# BOOSTXL-EDUMKII.net
KiCad netlist of a schematic drawn in EAGLE
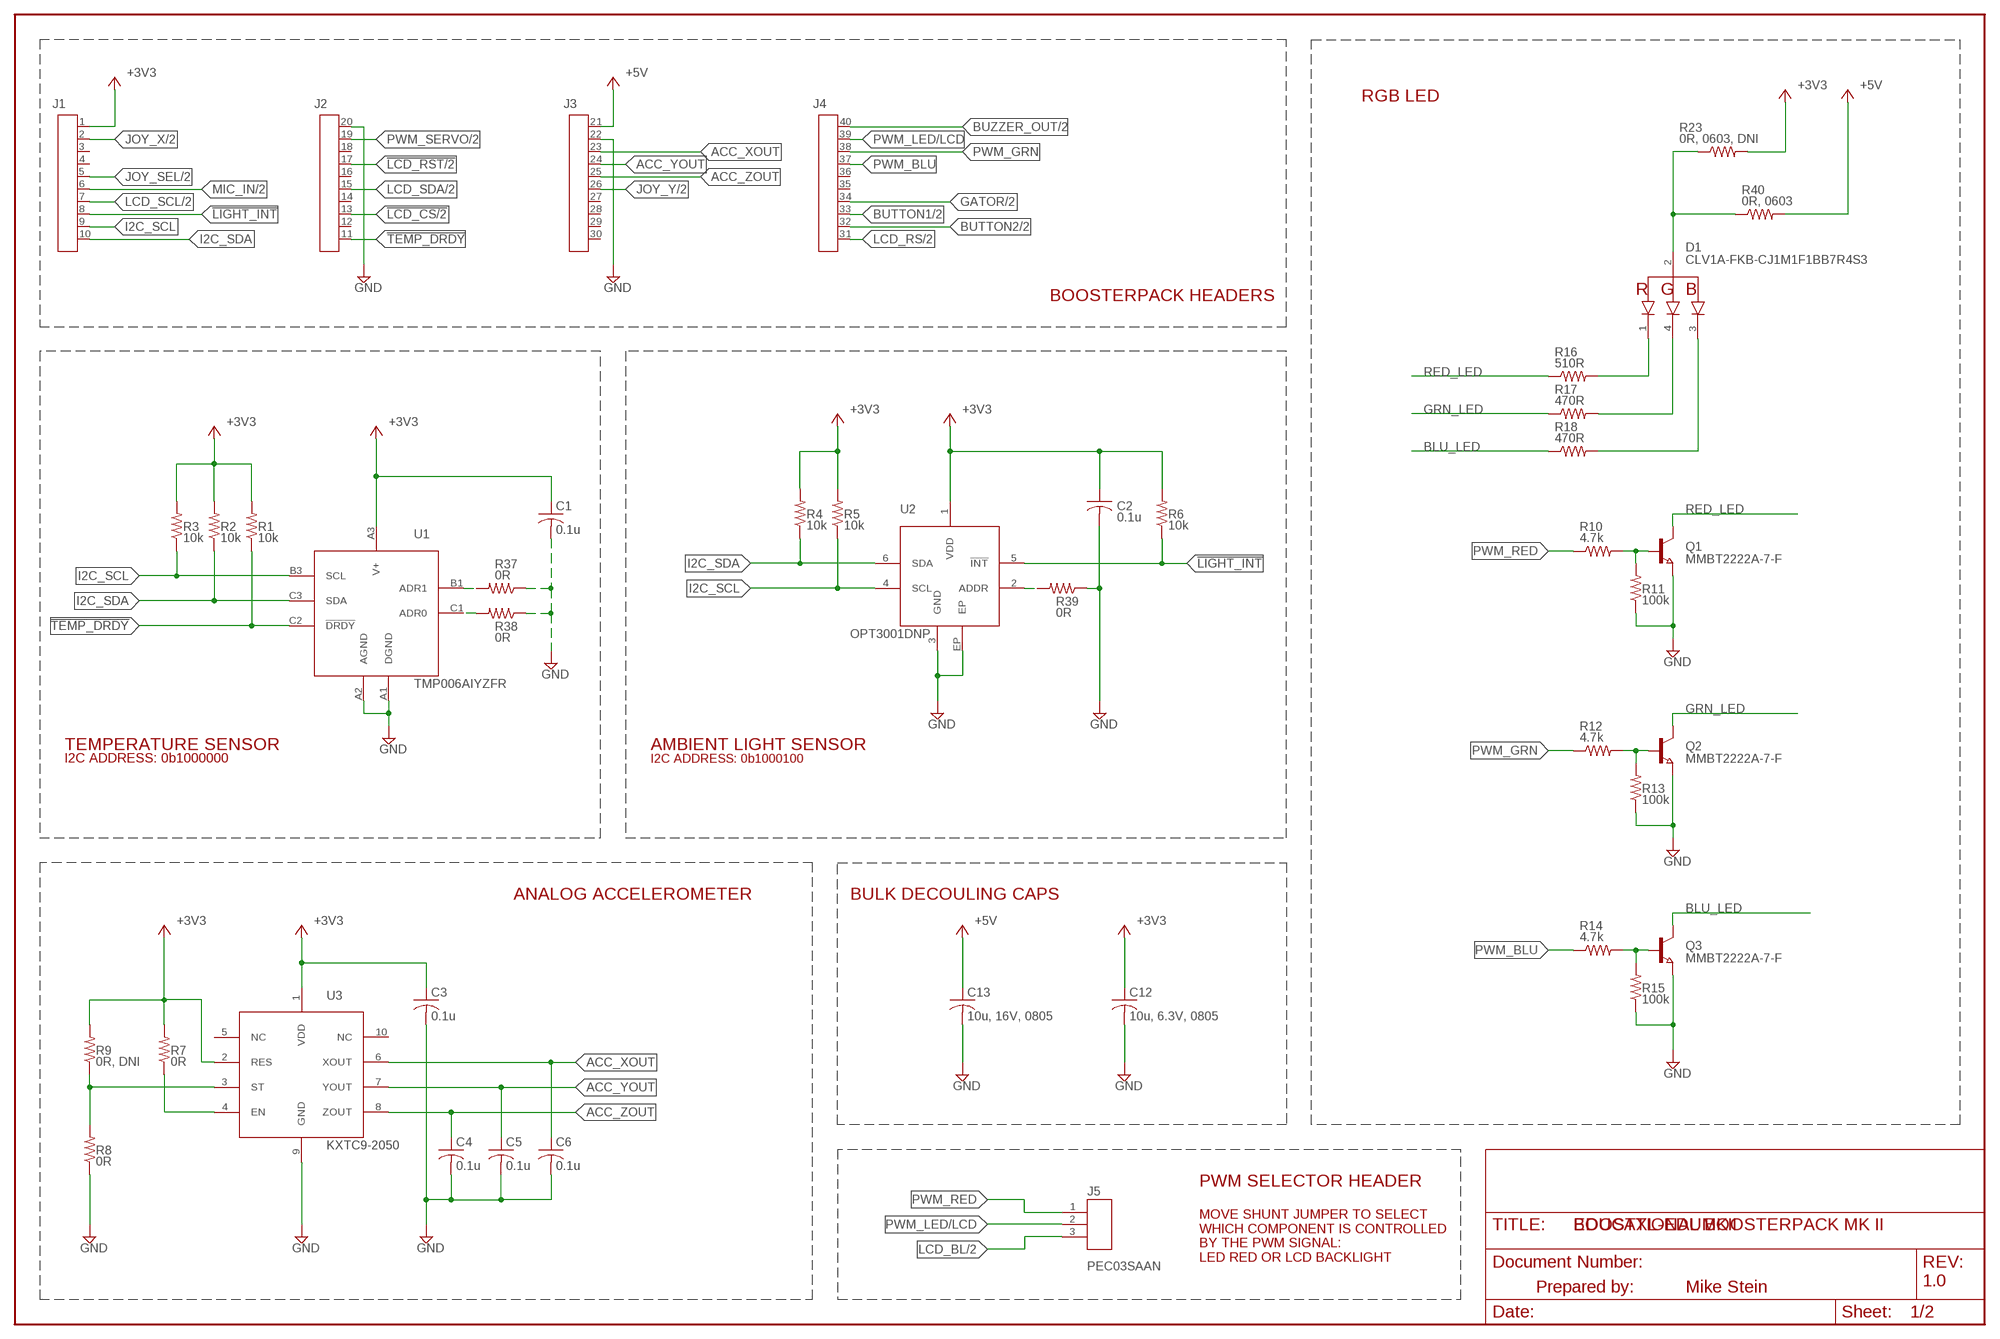
[diagram p0: schematic, sheet 1]
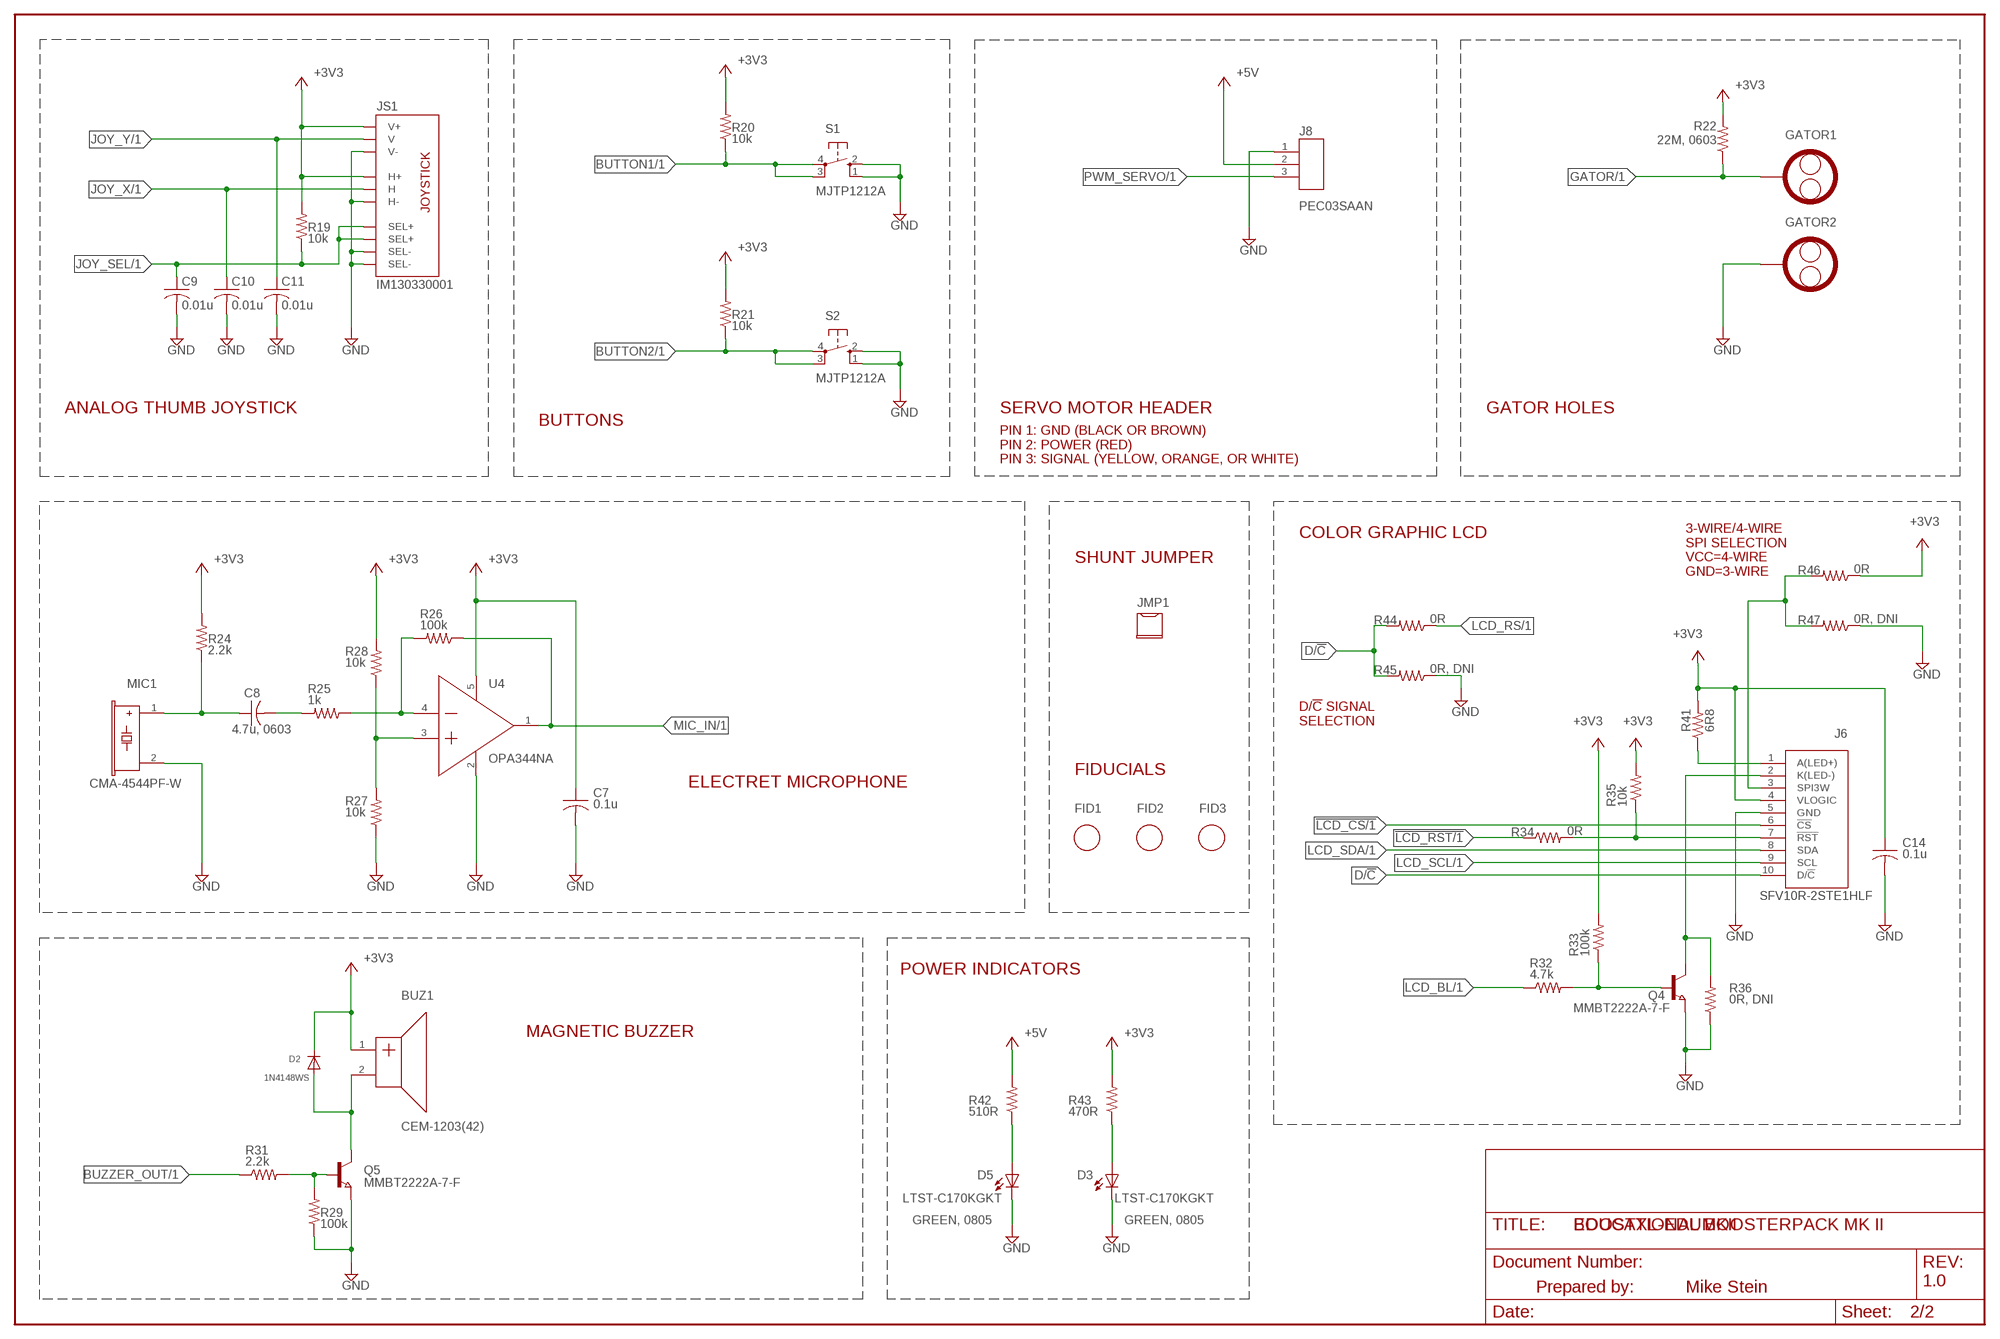
[diagram p1: schematic, sheet 2]

(export (version "E")
  (design (tool "Eeschema 10.0.6"))
  (components
    (comp (ref "C1")
      (value "0.1u")
      (footprint "eagle-import:0402")
      (libsource (lib "eagle-import") (part "C-USCM0402"))
    )
    (comp (ref "C2")
      (value "0.1u")
      (footprint "eagle-import:0402")
      (libsource (lib "eagle-import") (part "C-USCM0402"))
    )
    (comp (ref "C3")
      (value "0.1u")
      (footprint "eagle-import:0402")
      (libsource (lib "eagle-import") (part "C-USCM0402"))
    )
    (comp (ref "C4")
      (value "0.1u")
      (footprint "eagle-import:0402")
      (libsource (lib "eagle-import") (part "C-USCM0402"))
    )
    (comp (ref "C5")
      (value "0.1u")
      (footprint "eagle-import:0402")
      (libsource (lib "eagle-import") (part "C-USCM0402"))
    )
    (comp (ref "C6")
      (value "0.1u")
      (footprint "eagle-import:0402")
      (libsource (lib "eagle-import") (part "C-USCM0402"))
    )
    (comp (ref "C12")
      (value "10u, 6.3V, 0805")
      (footprint "eagle-import:C0805")
      (libsource (lib "eagle-import") (part "rcl_C-USC0805"))
    )
    (comp (ref "C13")
      (value "10u, 16V, 0805")
      (footprint "eagle-import:C0805")
      (libsource (lib "eagle-import") (part "rcl_C-USC0805"))
    )
    (comp (ref "D1")
      (value "CLV1A-FKB-CJ1M1F1BB7R4S3")
      (footprint "eagle-import:CLV1A-FKB")
      (libsource (lib "eagle-import") (part "CLV1A-FKB"))
    )
    (comp (ref "J1")
      (value "HEADER1X10")
      (footprint "eagle-import:1X10")
      (libsource (lib "eagle-import") (part "HEADER1X10"))
    )
    (comp (ref "J2")
      (value "HEADER1X10-J2")
      (footprint "eagle-import:1X10-J2")
      (libsource (lib "eagle-import") (part "HEADER1X10-J2"))
    )
    (comp (ref "J3")
      (value "HEADER1X10-J3")
      (footprint "eagle-import:1X10-J3")
      (libsource (lib "eagle-import") (part "HEADER1X10-J3"))
    )
    (comp (ref "J4")
      (value "HEADER1X10-J4")
      (footprint "eagle-import:1X10-J4")
      (libsource (lib "eagle-import") (part "HEADER1X10-J4"))
    )
    (comp (ref "J5")
      (value "PEC03SAAN")
      (footprint "eagle-import:1X03")
      (libsource (lib "eagle-import") (part "HEADER1X03"))
    )
    (comp (ref "Q1")
      (value "MMBT2222A-7-F")
      (footprint "eagle-import:SOT23")
      (libsource (lib "eagle-import") (part "NPN-TRANSISTOR_SOT23"))
    )
    (comp (ref "Q2")
      (value "MMBT2222A-7-F")
      (footprint "eagle-import:SOT23")
      (libsource (lib "eagle-import") (part "NPN-TRANSISTOR_SOT23"))
    )
    (comp (ref "Q3")
      (value "MMBT2222A-7-F")
      (footprint "eagle-import:SOT23")
      (libsource (lib "eagle-import") (part "NPN-TRANSISTOR_SOT23"))
    )
    (comp (ref "R1")
      (value "10k")
      (footprint "eagle-import:0402")
      (libsource (lib "eagle-import") (part "R-US_RM0402"))
    )
    (comp (ref "R2")
      (value "10k")
      (footprint "eagle-import:0402")
      (libsource (lib "eagle-import") (part "R-US_RM0402"))
    )
    (comp (ref "R3")
      (value "10k")
      (footprint "eagle-import:0402")
      (libsource (lib "eagle-import") (part "R-US_RM0402"))
    )
    (comp (ref "R4")
      (value "10k")
      (footprint "eagle-import:0402")
      (libsource (lib "eagle-import") (part "R-US_RM0402"))
    )
    (comp (ref "R5")
      (value "10k")
      (footprint "eagle-import:0402")
      (libsource (lib "eagle-import") (part "R-US_RM0402"))
    )
    (comp (ref "R6")
      (value "10k")
      (footprint "eagle-import:0402")
      (libsource (lib "eagle-import") (part "R-US_RM0402"))
    )
    (comp (ref "R7")
      (value "0R")
      (footprint "eagle-import:0402")
      (libsource (lib "eagle-import") (part "R-US_RM0402"))
    )
    (comp (ref "R8")
      (value "0R")
      (footprint "eagle-import:0402")
      (libsource (lib "eagle-import") (part "R-US_RM0402"))
    )
    (comp (ref "R9")
      (value "0R, DNI")
      (footprint "eagle-import:0402")
      (libsource (lib "eagle-import") (part "R-US_RM0402"))
    )
    (comp (ref "R10")
      (value "4.7k")
      (footprint "eagle-import:0402")
      (libsource (lib "eagle-import") (part "R-US_RM0402"))
    )
    (comp (ref "R11")
      (value "100k")
      (footprint "eagle-import:0402")
      (libsource (lib "eagle-import") (part "R-US_RM0402"))
    )
    (comp (ref "R12")
      (value "4.7k")
      (footprint "eagle-import:0402")
      (libsource (lib "eagle-import") (part "R-US_RM0402"))
    )
    (comp (ref "R13")
      (value "100k")
      (footprint "eagle-import:0402")
      (libsource (lib "eagle-import") (part "R-US_RM0402"))
    )
    (comp (ref "R14")
      (value "4.7k")
      (footprint "eagle-import:0402")
      (libsource (lib "eagle-import") (part "R-US_RM0402"))
    )
    (comp (ref "R15")
      (value "100k")
      (footprint "eagle-import:0402")
      (libsource (lib "eagle-import") (part "R-US_RM0402"))
    )
    (comp (ref "R16")
      (value "510R")
      (footprint "eagle-import:0402")
      (libsource (lib "eagle-import") (part "R-US_RM0402"))
    )
    (comp (ref "R17")
      (value "470R")
      (footprint "eagle-import:0402")
      (libsource (lib "eagle-import") (part "R-US_RM0402"))
    )
    (comp (ref "R18")
      (value "470R")
      (footprint "eagle-import:0402")
      (libsource (lib "eagle-import") (part "R-US_RM0402"))
    )
    (comp (ref "R23")
      (value "0R, 0603, DNI")
      (footprint "eagle-import:R0603")
      (libsource (lib "eagle-import") (part "R-US_R0603"))
    )
    (comp (ref "R37")
      (value "0R")
      (footprint "eagle-import:0402")
      (libsource (lib "eagle-import") (part "R-US_RM0402"))
    )
    (comp (ref "R38")
      (value "0R")
      (footprint "eagle-import:0402")
      (libsource (lib "eagle-import") (part "R-US_RM0402"))
    )
    (comp (ref "R39")
      (value "0R")
      (footprint "eagle-import:0402")
      (libsource (lib "eagle-import") (part "R-US_RM0402"))
    )
    (comp (ref "R40")
      (value "0R, 0603")
      (footprint "eagle-import:R0603")
      (libsource (lib "eagle-import") (part "R-US_R0603"))
    )
    (comp (ref "U1")
      (value "TMP006AIYZFR")
      (footprint "eagle-import:YZF_S-XBGA-N8")
      (libsource (lib "eagle-import") (part "TMP006AIYZF"))
    )
    (comp (ref "U2")
      (value "OPT3001DNP")
      (footprint "eagle-import:DNP_S-PWSON-N6")
      (libsource (lib "eagle-import") (part "OPT3001DNP"))
    )
    (comp (ref "U3")
      (value "KXTC9-2050")
      (footprint "eagle-import:KXTC9-2050")
      (libsource (lib "eagle-import") (part "KXTC9-2050"))
    )
    (comp (ref "BUZ1")
      (value "CEM-1203(42)")
      (footprint "eagle-import:CEM-1203(42)")
      (libsource (lib "eagle-import") (part "CEM-1203(42)"))
    )
    (comp (ref "C7")
      (value "0.1u")
      (footprint "eagle-import:0402")
      (libsource (lib "eagle-import") (part "C-USCM0402"))
    )
    (comp (ref "C8")
      (value "4.7u, 0603")
      (footprint "eagle-import:C0603")
      (libsource (lib "eagle-import") (part "C-USC0603"))
    )
    (comp (ref "C9")
      (value "0.01u")
      (footprint "eagle-import:0402")
      (libsource (lib "eagle-import") (part "C-USCM0402"))
    )
    (comp (ref "C10")
      (value "0.01u")
      (footprint "eagle-import:0402")
      (libsource (lib "eagle-import") (part "C-USCM0402"))
    )
    (comp (ref "C11")
      (value "0.01u")
      (footprint "eagle-import:0402")
      (libsource (lib "eagle-import") (part "C-USCM0402"))
    )
    (comp (ref "C14")
      (value "0.1u")
      (footprint "eagle-import:0402")
      (libsource (lib "eagle-import") (part "C-USCM0402"))
    )
    (comp (ref "D2")
      (value "1N4148WS")
      (footprint "eagle-import:SOD-323F")
      (libsource (lib "eagle-import") (part "DIODE"))
    )
    (comp (ref "D3")
      (value "LTST-C170KGKT")
      (footprint "eagle-import:LED-CHIP0805")
      (libsource (lib "eagle-import") (part "LED"))
    )
    (comp (ref "D5")
      (value "LTST-C170KGKT")
      (footprint "eagle-import:LED-CHIP0805")
      (libsource (lib "eagle-import") (part "LED"))
    )
    (comp (ref "FID1")
      (value "FIDUCIAL")
      (footprint "eagle-import:FIDUCIAL_1MM")
      (libsource (lib "eagle-import") (part "FIDUCIAL"))
    )
    (comp (ref "FID2")
      (value "FIDUCIAL")
      (footprint "eagle-import:FIDUCIAL_1MM")
      (libsource (lib "eagle-import") (part "FIDUCIAL"))
    )
    (comp (ref "FID3")
      (value "FIDUCIAL")
      (footprint "eagle-import:FIDUCIAL_1MM")
      (libsource (lib "eagle-import") (part "FIDUCIAL"))
    )
    (comp (ref "GATOR1")
      (value "GATOR_HOLE")
      (footprint "eagle-import:GATOR-HOLE-3MM")
      (libsource (lib "eagle-import") (part "GATOR_HOLE"))
    )
    (comp (ref "GATOR2")
      (value "GATOR_HOLE")
      (footprint "eagle-import:GATOR-HOLE-3MM")
      (libsource (lib "eagle-import") (part "GATOR_HOLE"))
    )
    (comp (ref "J6")
      (value "SFV10R-2STE1HLF")
      (footprint "eagle-import:SFV10R-2STE1HLF")
      (libsource (lib "eagle-import") (part "SFV10R-2STE1HLF"))
    )
    (comp (ref "J8")
      (value "PEC03SAAN")
      (footprint "eagle-import:1X03")
      (libsource (lib "eagle-import") (part "HEADER1X03"))
    )
    (comp (ref "JS1")
      (value "IM130330001")
      (footprint "eagle-import:JOYSTICK-SW")
      (libsource (lib "eagle-import") (part "JOYSTICK-SW"))
    )
    (comp (ref "MIC1")
      (value "CMA-4544PF-W")
      (footprint "eagle-import:CMA-4544PF-W")
      (libsource (lib "eagle-import") (part "CMA-4544PF-W"))
    )
    (comp (ref "Q4")
      (value "MMBT2222A-7-F")
      (footprint "eagle-import:SOT23")
      (libsource (lib "eagle-import") (part "NPN-TRANSISTOR_SOT23"))
    )
    (comp (ref "Q5")
      (value "MMBT2222A-7-F")
      (footprint "eagle-import:SOT23")
      (libsource (lib "eagle-import") (part "NPN-TRANSISTOR_SOT23"))
    )
    (comp (ref "R19")
      (value "10k")
      (footprint "eagle-import:0402")
      (libsource (lib "eagle-import") (part "R-US_RM0402"))
    )
    (comp (ref "R20")
      (value "10k")
      (footprint "eagle-import:0402")
      (libsource (lib "eagle-import") (part "R-US_RM0402"))
    )
    (comp (ref "R21")
      (value "10k")
      (footprint "eagle-import:0402")
      (libsource (lib "eagle-import") (part "R-US_RM0402"))
    )
    (comp (ref "R22")
      (value "22M, 0603")
      (footprint "eagle-import:R0603")
      (libsource (lib "eagle-import") (part "R-US_R0603"))
    )
    (comp (ref "R24")
      (value "2.2k")
      (footprint "eagle-import:0402")
      (libsource (lib "eagle-import") (part "R-US_RM0402"))
    )
    (comp (ref "R25")
      (value "1k")
      (footprint "eagle-import:0402")
      (libsource (lib "eagle-import") (part "R-US_RM0402"))
    )
    (comp (ref "R26")
      (value "100k")
      (footprint "eagle-import:0402")
      (libsource (lib "eagle-import") (part "R-US_RM0402"))
    )
    (comp (ref "R27")
      (value "10k")
      (footprint "eagle-import:0402")
      (libsource (lib "eagle-import") (part "R-US_RM0402"))
    )
    (comp (ref "R28")
      (value "10k")
      (footprint "eagle-import:0402")
      (libsource (lib "eagle-import") (part "R-US_RM0402"))
    )
    (comp (ref "R29")
      (value "100k")
      (footprint "eagle-import:0402")
      (libsource (lib "eagle-import") (part "R-US_RM0402"))
    )
    (comp (ref "R31")
      (value "2.2k")
      (footprint "eagle-import:0402")
      (libsource (lib "eagle-import") (part "R-US_RM0402"))
    )
    (comp (ref "R32")
      (value "4.7k")
      (footprint "eagle-import:0402")
      (libsource (lib "eagle-import") (part "R-US_RM0402"))
    )
    (comp (ref "R33")
      (value "100k")
      (footprint "eagle-import:0402")
      (libsource (lib "eagle-import") (part "R-US_RM0402"))
    )
    (comp (ref "R34")
      (value "0R")
      (footprint "eagle-import:0402")
      (libsource (lib "eagle-import") (part "R-US_RM0402"))
    )
    (comp (ref "R35")
      (value "10k")
      (footprint "eagle-import:0402")
      (libsource (lib "eagle-import") (part "R-US_RM0402"))
    )
    (comp (ref "R36")
      (value "0R, DNI")
      (footprint "eagle-import:0402")
      (libsource (lib "eagle-import") (part "R-US_RM0402"))
    )
    (comp (ref "R41")
      (value "6R8")
      (footprint "eagle-import:0402")
      (libsource (lib "eagle-import") (part "R-US_RM0402"))
    )
    (comp (ref "R42")
      (value "510R")
      (footprint "eagle-import:0402")
      (libsource (lib "eagle-import") (part "R-US_RM0402"))
    )
    (comp (ref "R43")
      (value "470R")
      (footprint "eagle-import:0402")
      (libsource (lib "eagle-import") (part "R-US_RM0402"))
    )
    (comp (ref "R44")
      (value "0R")
      (footprint "eagle-import:0402")
      (libsource (lib "eagle-import") (part "R-US_RM0402"))
    )
    (comp (ref "R45")
      (value "0R, DNI")
      (footprint "eagle-import:0402")
      (libsource (lib "eagle-import") (part "R-US_RM0402"))
    )
    (comp (ref "R46")
      (value "0R")
      (footprint "eagle-import:0402")
      (libsource (lib "eagle-import") (part "R-US_RM0402"))
    )
    (comp (ref "R47")
      (value "0R, DNI")
      (footprint "eagle-import:0402")
      (libsource (lib "eagle-import") (part "R-US_RM0402"))
    )
    (comp (ref "S1")
      (value "MJTP1212A")
      (footprint "eagle-import:TACTILE-MJTP")
      (libsource (lib "eagle-import") (part "SWITCH-MJTP"))
    )
    (comp (ref "S2")
      (value "MJTP1212A")
      (footprint "eagle-import:TACTILE-MJTP")
      (libsource (lib "eagle-import") (part "SWITCH-MJTP"))
    )
    (comp (ref "U4")
      (value "OPA344NA")
      (footprint "eagle-import:DBV_R-PDSO-G5")
      (libsource (lib "eagle-import") (part "OPA344NA"))
    )
  )
  (nets
    (net (code "1") (name "+3V3") (class "Default")
      (node (ref "BUZ1") (pin "1") (pinfunction "SPKR_P_1") (pintype "passive"))
      (node (ref "C1") (pin "1") (pinfunction "1_1") (pintype "passive"))
      (node (ref "C12") (pin "1") (pinfunction "1_1") (pintype "passive"))
      (node (ref "C14") (pin "1") (pinfunction "1_1") (pintype "passive"))
      (node (ref "C2") (pin "1") (pinfunction "1_1") (pintype "passive"))
      (node (ref "C3") (pin "1") (pinfunction "1_1") (pintype "passive"))
      (node (ref "C7") (pin "1") (pinfunction "1_1") (pintype "passive"))
      (node (ref "D2") (pin "C") (pinfunction "C_C") (pintype "passive"))
      (node (ref "J1") (pin "1") (pinfunction "1_1") (pintype "bidirectional"))
      (node (ref "J6") (pin "4") (pinfunction "VLOGIC_4") (pintype "power_in"))
      (node (ref "JS1") (pin "H+") (pinfunction "H+_H+") (pintype "bidirectional"))
      (node (ref "JS1") (pin "V+") (pinfunction "V+_V+") (pintype "bidirectional"))
      (node (ref "R1") (pin "2") (pinfunction "2_2") (pintype "passive"))
      (node (ref "R19") (pin "2") (pinfunction "2_2") (pintype "passive"))
      (node (ref "R2") (pin "2") (pinfunction "2_2") (pintype "passive"))
      (node (ref "R20") (pin "2") (pinfunction "2_2") (pintype "passive"))
      (node (ref "R21") (pin "2") (pinfunction "2_2") (pintype "passive"))
      (node (ref "R22") (pin "2") (pinfunction "2_2") (pintype "passive"))
      (node (ref "R23") (pin "2") (pinfunction "2_2") (pintype "passive"))
      (node (ref "R24") (pin "2") (pinfunction "2_2") (pintype "passive"))
      (node (ref "R28") (pin "2") (pinfunction "2_2") (pintype "passive"))
      (node (ref "R3") (pin "2") (pinfunction "2_2") (pintype "passive"))
      (node (ref "R33") (pin "2") (pinfunction "2_2") (pintype "passive"))
      (node (ref "R35") (pin "2") (pinfunction "2_2") (pintype "passive"))
      (node (ref "R4") (pin "2") (pinfunction "2_2") (pintype "passive"))
      (node (ref "R41") (pin "2") (pinfunction "2_2") (pintype "passive"))
      (node (ref "R43") (pin "2") (pinfunction "2_2") (pintype "passive"))
      (node (ref "R46") (pin "1") (pinfunction "1_1") (pintype "passive"))
      (node (ref "R5") (pin "2") (pinfunction "2_2") (pintype "passive"))
      (node (ref "R6") (pin "2") (pinfunction "2_2") (pintype "passive"))
      (node (ref "R7") (pin "2") (pinfunction "2_2") (pintype "passive"))
      (node (ref "R9") (pin "2") (pinfunction "2_2") (pintype "passive"))
      (node (ref "U1") (pin "A3") (pinfunction "V+_A3") (pintype "power_in"))
      (node (ref "U2") (pin "1") (pinfunction "VDD_1") (pintype "power_in"))
      (node (ref "U3") (pin "1") (pinfunction "VDD_1") (pintype "power_in"))
      (node (ref "U3") (pin "2") (pinfunction "RES_2") (pintype "power_in"))
      (node (ref "U4") (pin "5") (pinfunction "V+_5") (pintype "power_in"))
    )
    (net (code "2") (name "+5V") (class "Default")
      (node (ref "C13") (pin "1") (pinfunction "1_1") (pintype "passive"))
      (node (ref "J3") (pin "21") (pinfunction "1_21") (pintype "bidirectional"))
      (node (ref "J8") (pin "2") (pinfunction "2_2") (pintype "bidirectional"))
      (node (ref "R40") (pin "2") (pinfunction "2_2") (pintype "passive"))
      (node (ref "R42") (pin "2") (pinfunction "2_2") (pintype "passive"))
    )
    (net (code "3") (name "ACC_XOUT") (class "Default")
      (node (ref "C6") (pin "1") (pinfunction "1_1") (pintype "passive"))
      (node (ref "J3") (pin "23") (pinfunction "3_23") (pintype "bidirectional"))
      (node (ref "U3") (pin "6") (pinfunction "XOUT_6") (pintype "output"))
    )
    (net (code "4") (name "ACC_YOUT") (class "Default")
      (node (ref "C5") (pin "1") (pinfunction "1_1") (pintype "passive"))
      (node (ref "J3") (pin "24") (pinfunction "4_24") (pintype "bidirectional"))
      (node (ref "U3") (pin "7") (pinfunction "YOUT_7") (pintype "output"))
    )
    (net (code "5") (name "ACC_ZOUT") (class "Default")
      (node (ref "C4") (pin "1") (pinfunction "1_1") (pintype "passive"))
      (node (ref "J3") (pin "25") (pinfunction "5_25") (pintype "bidirectional"))
      (node (ref "U3") (pin "8") (pinfunction "ZOUT_8") (pintype "output"))
    )
    (net (code "6") (name "BLU_LED") (class "Default")
      (node (ref "Q3") (pin "3") (pinfunction "C_3") (pintype "passive"))
      (node (ref "R18") (pin "1") (pinfunction "1_1") (pintype "passive"))
    )
    (net (code "7") (name "BUTTON1") (class "Default")
      (node (ref "J4") (pin "33") (pinfunction "8_33") (pintype "bidirectional"))
      (node (ref "R20") (pin "1") (pinfunction "1_1") (pintype "passive"))
      (node (ref "S1") (pin "3") (pinfunction "P1_3") (pintype "passive"))
      (node (ref "S1") (pin "4") (pinfunction "P_4") (pintype "passive"))
    )
    (net (code "8") (name "BUTTON2") (class "Default")
      (node (ref "J4") (pin "32") (pinfunction "9_32") (pintype "bidirectional"))
      (node (ref "R21") (pin "1") (pinfunction "1_1") (pintype "passive"))
      (node (ref "S2") (pin "3") (pinfunction "P1_3") (pintype "passive"))
      (node (ref "S2") (pin "4") (pinfunction "P_4") (pintype "passive"))
    )
    (net (code "9") (name "BUZZER_OUT") (class "Default")
      (node (ref "J4") (pin "40") (pinfunction "1_40") (pintype "bidirectional"))
      (node (ref "R31") (pin "1") (pinfunction "1_1") (pintype "passive"))
    )
    (net (code "10") (name "D{slash}~{C}") (class "Default")
      (node (ref "J6") (pin "10") (pinfunction "D/~{C}_10") (pintype "bidirectional"))
      (node (ref "R44") (pin "2") (pinfunction "2_2") (pintype "passive"))
      (node (ref "R45") (pin "2") (pinfunction "2_2") (pintype "passive"))
    )
    (net (code "11") (name "GATOR") (class "Default")
      (node (ref "GATOR1") (pin "1@1") (pinfunction "P$1_1@1") (pintype "bidirectional"))
      (node (ref "J4") (pin "34") (pinfunction "7_34") (pintype "bidirectional"))
      (node (ref "R22") (pin "1") (pinfunction "1_1") (pintype "passive"))
    )
    (net (code "12") (name "GND") (class "Default")
      (node (ref "C1") (pin "2") (pinfunction "2_2") (pintype "passive"))
      (node (ref "C10") (pin "2") (pinfunction "2_2") (pintype "passive"))
      (node (ref "C11") (pin "2") (pinfunction "2_2") (pintype "passive"))
      (node (ref "C12") (pin "2") (pinfunction "2_2") (pintype "passive"))
      (node (ref "C13") (pin "2") (pinfunction "2_2") (pintype "passive"))
      (node (ref "C14") (pin "2") (pinfunction "2_2") (pintype "passive"))
      (node (ref "C2") (pin "2") (pinfunction "2_2") (pintype "passive"))
      (node (ref "C3") (pin "2") (pinfunction "2_2") (pintype "passive"))
      (node (ref "C4") (pin "2") (pinfunction "2_2") (pintype "passive"))
      (node (ref "C5") (pin "2") (pinfunction "2_2") (pintype "passive"))
      (node (ref "C6") (pin "2") (pinfunction "2_2") (pintype "passive"))
      (node (ref "C7") (pin "2") (pinfunction "2_2") (pintype "passive"))
      (node (ref "C9") (pin "2") (pinfunction "2_2") (pintype "passive"))
      (node (ref "D3") (pin "C") (pinfunction "C_C") (pintype "passive"))
      (node (ref "D5") (pin "C") (pinfunction "C_C") (pintype "passive"))
      (node (ref "GATOR2") (pin "1@1") (pinfunction "P$1_1@1") (pintype "bidirectional"))
      (node (ref "J2") (pin "20") (pinfunction "1_20") (pintype "bidirectional"))
      (node (ref "J3") (pin "22") (pinfunction "2_22") (pintype "bidirectional"))
      (node (ref "J6") (pin "5") (pinfunction "GND_5") (pintype "bidirectional"))
      (node (ref "J8") (pin "1") (pinfunction "1_1") (pintype "bidirectional"))
      (node (ref "JS1") (pin "H-") (pinfunction "H-_H-") (pintype "bidirectional"))
      (node (ref "JS1") (pin "SEL-1") (pinfunction "SEL-_SEL-1") (pintype "bidirectional"))
      (node (ref "JS1") (pin "SEL-2") (pinfunction "SEL-_SEL-2") (pintype "bidirectional"))
      (node (ref "JS1") (pin "V-") (pinfunction "V-_V-") (pintype "bidirectional"))
      (node (ref "MIC1") (pin "2") (pinfunction "NEG_2") (pintype "bidirectional"))
      (node (ref "Q1") (pin "2") (pinfunction "E_2") (pintype "passive"))
      (node (ref "Q2") (pin "2") (pinfunction "E_2") (pintype "passive"))
      (node (ref "Q3") (pin "2") (pinfunction "E_2") (pintype "passive"))
      (node (ref "Q4") (pin "2") (pinfunction "E_2") (pintype "passive"))
      (node (ref "Q5") (pin "2") (pinfunction "E_2") (pintype "passive"))
      (node (ref "R11") (pin "1") (pinfunction "1_1") (pintype "passive"))
      (node (ref "R13") (pin "1") (pinfunction "1_1") (pintype "passive"))
      (node (ref "R15") (pin "1") (pinfunction "1_1") (pintype "passive"))
      (node (ref "R27") (pin "1") (pinfunction "1_1") (pintype "passive"))
      (node (ref "R29") (pin "1") (pinfunction "1_1") (pintype "passive"))
      (node (ref "R36") (pin "1") (pinfunction "1_1") (pintype "passive"))
      (node (ref "R37") (pin "1") (pinfunction "1_1") (pintype "passive"))
      (node (ref "R38") (pin "1") (pinfunction "1_1") (pintype "passive"))
      (node (ref "R39") (pin "1") (pinfunction "1_1") (pintype "passive"))
      (node (ref "R45") (pin "1") (pinfunction "1_1") (pintype "passive"))
      (node (ref "R47") (pin "1") (pinfunction "1_1") (pintype "passive"))
      (node (ref "R8") (pin "1") (pinfunction "1_1") (pintype "passive"))
      (node (ref "S1") (pin "1") (pinfunction "S1_1") (pintype "passive"))
      (node (ref "S1") (pin "2") (pinfunction "S_2") (pintype "passive"))
      (node (ref "S2") (pin "1") (pinfunction "S1_1") (pintype "passive"))
      (node (ref "S2") (pin "2") (pinfunction "S_2") (pintype "passive"))
      (node (ref "U1") (pin "A1") (pinfunction "DGND_A1") (pintype "power_in"))
      (node (ref "U1") (pin "A2") (pinfunction "AGND_A2") (pintype "power_in"))
      (node (ref "U2") (pin "3") (pinfunction "GND_3") (pintype "power_in"))
      (node (ref "U2") (pin "EP") (pinfunction "EP_EP") (pintype "power_in"))
      (node (ref "U3") (pin "9") (pinfunction "GND_9") (pintype "power_in"))
      (node (ref "U4") (pin "2") (pinfunction "V-_2") (pintype "power_in"))
    )
    (net (code "13") (name "GRN_LED") (class "Default")
      (node (ref "Q2") (pin "3") (pinfunction "C_3") (pintype "passive"))
      (node (ref "R17") (pin "1") (pinfunction "1_1") (pintype "passive"))
    )
    (net (code "14") (name "I2C_SCL") (class "Default")
      (node (ref "J1") (pin "9") (pinfunction "9_9") (pintype "bidirectional"))
      (node (ref "R3") (pin "1") (pinfunction "1_1") (pintype "passive"))
      (node (ref "R5") (pin "1") (pinfunction "1_1") (pintype "passive"))
      (node (ref "U1") (pin "B3") (pinfunction "SCL_B3") (pintype "input"))
      (node (ref "U2") (pin "4") (pinfunction "SCL_4") (pintype "input"))
    )
    (net (code "15") (name "I2C_SDA") (class "Default")
      (node (ref "J1") (pin "10") (pinfunction "10_10") (pintype "bidirectional"))
      (node (ref "R2") (pin "1") (pinfunction "1_1") (pintype "passive"))
      (node (ref "R4") (pin "1") (pinfunction "1_1") (pintype "passive"))
      (node (ref "U1") (pin "C3") (pinfunction "SDA_C3") (pintype "bidirectional"))
      (node (ref "U2") (pin "6") (pinfunction "SDA_6") (pintype "bidirectional"))
    )
    (net (code "16") (name "JOY_SEL") (class "Default")
      (node (ref "C9") (pin "1") (pinfunction "1_1") (pintype "passive"))
      (node (ref "J1") (pin "5") (pinfunction "5_5") (pintype "bidirectional"))
      (node (ref "JS1") (pin "SEL+1") (pinfunction "SEL+_SEL+1") (pintype "bidirectional"))
      (node (ref "JS1") (pin "SEL+2") (pinfunction "SEL+_SEL+2") (pintype "bidirectional"))
      (node (ref "R19") (pin "1") (pinfunction "1_1") (pintype "passive"))
    )
    (net (code "17") (name "JOY_X") (class "Default")
      (node (ref "C10") (pin "1") (pinfunction "1_1") (pintype "passive"))
      (node (ref "J1") (pin "2") (pinfunction "2_2") (pintype "bidirectional"))
      (node (ref "JS1") (pin "H") (pinfunction "H_H") (pintype "bidirectional"))
    )
    (net (code "18") (name "JOY_Y") (class "Default")
      (node (ref "C11") (pin "1") (pinfunction "1_1") (pintype "passive"))
      (node (ref "J3") (pin "26") (pinfunction "6_26") (pintype "bidirectional"))
      (node (ref "JS1") (pin "V") (pinfunction "V_V") (pintype "bidirectional"))
    )
    (net (code "19") (name "LCD_BL") (class "Default")
      (node (ref "J5") (pin "3") (pinfunction "3_3") (pintype "bidirectional"))
      (node (ref "R32") (pin "1") (pinfunction "1_1") (pintype "passive"))
    )
    (net (code "20") (name "LCD_RS") (class "Default")
      (node (ref "J4") (pin "31") (pinfunction "10_31") (pintype "bidirectional"))
      (node (ref "R44") (pin "1") (pinfunction "1_1") (pintype "passive"))
    )
    (net (code "21") (name "LCD_SCL") (class "Default")
      (node (ref "J1") (pin "7") (pinfunction "7_7") (pintype "bidirectional"))
      (node (ref "J6") (pin "9") (pinfunction "SCL_9") (pintype "bidirectional"))
    )
    (net (code "22") (name "LCD_SDA") (class "Default")
      (node (ref "J2") (pin "15") (pinfunction "6_15") (pintype "bidirectional"))
      (node (ref "J6") (pin "8") (pinfunction "SDA_8") (pintype "bidirectional"))
    )
    (net (code "23") (name "MIC_IN") (class "Default")
      (node (ref "J1") (pin "6") (pinfunction "6_6") (pintype "bidirectional"))
      (node (ref "R26") (pin "1") (pinfunction "1_1") (pintype "passive"))
      (node (ref "U4") (pin "1") (pinfunction "OUT_1") (pintype "bidirectional"))
    )
    (net (code "24") (name "Net-(BUZ1-SPKR_N)") (class "Default")
      (node (ref "BUZ1") (pin "2") (pinfunction "SPKR_N_2") (pintype "passive"))
      (node (ref "D2") (pin "A") (pinfunction "A_A") (pintype "passive"))
      (node (ref "Q5") (pin "3") (pinfunction "C_3") (pintype "passive"))
    )
    (net (code "25") (name "Net-(C8-Pad2)") (class "Default")
      (node (ref "C8") (pin "2") (pinfunction "2_2") (pintype "passive"))
      (node (ref "R25") (pin "2") (pinfunction "2_2") (pintype "passive"))
    )
    (net (code "26") (name "Net-(D1-BLU)") (class "Default")
      (node (ref "D1") (pin "3") (pinfunction "BLU_3") (pintype "bidirectional"))
      (node (ref "R18") (pin "2") (pinfunction "2_2") (pintype "passive"))
    )
    (net (code "27") (name "Net-(D1-CA)") (class "Default")
      (node (ref "D1") (pin "2") (pinfunction "CA_2") (pintype "bidirectional"))
      (node (ref "R23") (pin "1") (pinfunction "1_1") (pintype "passive"))
      (node (ref "R40") (pin "1") (pinfunction "1_1") (pintype "passive"))
    )
    (net (code "28") (name "Net-(D1-GRN)") (class "Default")
      (node (ref "D1") (pin "4") (pinfunction "GRN_4") (pintype "bidirectional"))
      (node (ref "R17") (pin "2") (pinfunction "2_2") (pintype "passive"))
    )
    (net (code "29") (name "Net-(D1-RED)") (class "Default")
      (node (ref "D1") (pin "1") (pinfunction "RED_1") (pintype "bidirectional"))
      (node (ref "R16") (pin "2") (pinfunction "2_2") (pintype "passive"))
    )
    (net (code "30") (name "Net-(D3-PadA)") (class "Default")
      (node (ref "D3") (pin "A") (pinfunction "A_A") (pintype "passive"))
      (node (ref "R43") (pin "1") (pinfunction "1_1") (pintype "passive"))
    )
    (net (code "31") (name "Net-(D5-PadA)") (class "Default")
      (node (ref "D5") (pin "A") (pinfunction "A_A") (pintype "passive"))
      (node (ref "R42") (pin "1") (pinfunction "1_1") (pintype "passive"))
    )
    (net (code "32") (name "Net-(J6-A(LED+))") (class "Default")
      (node (ref "J6") (pin "1") (pinfunction "A(LED+)_1") (pintype "power_in"))
      (node (ref "R41") (pin "1") (pinfunction "1_1") (pintype "passive"))
    )
    (net (code "33") (name "Net-(J6-K(LED-))") (class "Default")
      (node (ref "J6") (pin "2") (pinfunction "K(LED-)_2") (pintype "bidirectional"))
      (node (ref "Q4") (pin "3") (pinfunction "C_3") (pintype "passive"))
      (node (ref "R36") (pin "2") (pinfunction "2_2") (pintype "passive"))
    )
    (net (code "34") (name "Net-(J6-SPI3W)") (class "Default")
      (node (ref "J6") (pin "3") (pinfunction "SPI3W_3") (pintype "bidirectional"))
      (node (ref "R46") (pin "2") (pinfunction "2_2") (pintype "passive"))
      (node (ref "R47") (pin "2") (pinfunction "2_2") (pintype "passive"))
    )
    (net (code "35") (name "Net-(J6-~{RST})") (class "Default")
      (node (ref "J6") (pin "7") (pinfunction "~{RST}_7") (pintype "bidirectional"))
      (node (ref "R34") (pin "2") (pinfunction "2_2") (pintype "passive"))
      (node (ref "R35") (pin "1") (pinfunction "1_1") (pintype "passive"))
    )
    (net (code "36") (name "Net-(MIC1-POS)") (class "Default")
      (node (ref "C8") (pin "1") (pinfunction "1_1") (pintype "passive"))
      (node (ref "MIC1") (pin "1") (pinfunction "POS_1") (pintype "bidirectional"))
      (node (ref "R24") (pin "1") (pinfunction "1_1") (pintype "passive"))
    )
    (net (code "37") (name "Net-(Q1-B)") (class "Default")
      (node (ref "Q1") (pin "1") (pinfunction "B_1") (pintype "passive"))
      (node (ref "R10") (pin "2") (pinfunction "2_2") (pintype "passive"))
      (node (ref "R11") (pin "2") (pinfunction "2_2") (pintype "passive"))
    )
    (net (code "38") (name "Net-(Q2-B)") (class "Default")
      (node (ref "Q2") (pin "1") (pinfunction "B_1") (pintype "passive"))
      (node (ref "R12") (pin "2") (pinfunction "2_2") (pintype "passive"))
      (node (ref "R13") (pin "2") (pinfunction "2_2") (pintype "passive"))
    )
    (net (code "39") (name "Net-(Q3-B)") (class "Default")
      (node (ref "Q3") (pin "1") (pinfunction "B_1") (pintype "passive"))
      (node (ref "R14") (pin "2") (pinfunction "2_2") (pintype "passive"))
      (node (ref "R15") (pin "2") (pinfunction "2_2") (pintype "passive"))
    )
    (net (code "40") (name "Net-(Q4-B)") (class "Default")
      (node (ref "Q4") (pin "1") (pinfunction "B_1") (pintype "passive"))
      (node (ref "R32") (pin "2") (pinfunction "2_2") (pintype "passive"))
      (node (ref "R33") (pin "1") (pinfunction "1_1") (pintype "passive"))
    )
    (net (code "41") (name "Net-(Q5-B)") (class "Default")
      (node (ref "Q5") (pin "1") (pinfunction "B_1") (pintype "passive"))
      (node (ref "R29") (pin "2") (pinfunction "2_2") (pintype "passive"))
      (node (ref "R31") (pin "2") (pinfunction "2_2") (pintype "passive"))
    )
    (net (code "42") (name "Net-(U1-ADR0)") (class "Default")
      (node (ref "R38") (pin "2") (pinfunction "2_2") (pintype "passive"))
      (node (ref "U1") (pin "C1") (pinfunction "ADR0_C1") (pintype "input"))
    )
    (net (code "43") (name "Net-(U1-ADR1)") (class "Default")
      (node (ref "R37") (pin "2") (pinfunction "2_2") (pintype "passive"))
      (node (ref "U1") (pin "B1") (pinfunction "ADR1_B1") (pintype "input"))
    )
    (net (code "44") (name "Net-(U2-ADDR)") (class "Default")
      (node (ref "R39") (pin "2") (pinfunction "2_2") (pintype "passive"))
      (node (ref "U2") (pin "2") (pinfunction "ADDR_2") (pintype "input"))
    )
    (net (code "45") (name "Net-(U3-EN)") (class "Default")
      (node (ref "R7") (pin "1") (pinfunction "1_1") (pintype "passive"))
      (node (ref "U3") (pin "4") (pinfunction "EN_4") (pintype "input"))
    )
    (net (code "46") (name "Net-(U3-ST)") (class "Default")
      (node (ref "R8") (pin "2") (pinfunction "2_2") (pintype "passive"))
      (node (ref "R9") (pin "1") (pinfunction "1_1") (pintype "passive"))
      (node (ref "U3") (pin "3") (pinfunction "ST_3") (pintype "input"))
    )
    (net (code "47") (name "Net-(U4-+IN)") (class "Default")
      (node (ref "R27") (pin "2") (pinfunction "2_2") (pintype "passive"))
      (node (ref "R28") (pin "1") (pinfunction "1_1") (pintype "passive"))
      (node (ref "U4") (pin "3") (pinfunction "+IN_3") (pintype "bidirectional"))
    )
    (net (code "48") (name "Net-(U4--IN)") (class "Default")
      (node (ref "R25") (pin "1") (pinfunction "1_1") (pintype "passive"))
      (node (ref "R26") (pin "2") (pinfunction "2_2") (pintype "passive"))
      (node (ref "U4") (pin "4") (pinfunction "-IN_4") (pintype "bidirectional"))
    )
    (net (code "49") (name "PWM_BLU") (class "Default")
      (node (ref "J4") (pin "37") (pinfunction "4_37") (pintype "bidirectional"))
      (node (ref "R14") (pin "1") (pinfunction "1_1") (pintype "passive"))
    )
    (net (code "50") (name "PWM_GRN") (class "Default")
      (node (ref "J4") (pin "38") (pinfunction "3_38") (pintype "bidirectional"))
      (node (ref "R12") (pin "1") (pinfunction "1_1") (pintype "passive"))
    )
    (net (code "51") (name "PWM_LED{slash}LCD") (class "Default")
      (node (ref "J4") (pin "39") (pinfunction "2_39") (pintype "bidirectional"))
      (node (ref "J5") (pin "2") (pinfunction "2_2") (pintype "bidirectional"))
    )
    (net (code "52") (name "PWM_RED") (class "Default")
      (node (ref "J5") (pin "1") (pinfunction "1_1") (pintype "bidirectional"))
      (node (ref "R10") (pin "1") (pinfunction "1_1") (pintype "passive"))
    )
    (net (code "53") (name "PWM_SERVO") (class "Default")
      (node (ref "J2") (pin "19") (pinfunction "2_19") (pintype "bidirectional"))
      (node (ref "J8") (pin "3") (pinfunction "3_3") (pintype "bidirectional"))
    )
    (net (code "54") (name "RED_LED") (class "Default")
      (node (ref "Q1") (pin "3") (pinfunction "C_3") (pintype "passive"))
      (node (ref "R16") (pin "1") (pinfunction "1_1") (pintype "passive"))
    )
    (net (code "55") (name "unconnected-(J1-Pad3)") (class "Default")
      (node (ref "J1") (pin "3") (pinfunction "3_3") (pintype "bidirectional"))
    )
    (net (code "56") (name "unconnected-(J1-Pad4)") (class "Default")
      (node (ref "J1") (pin "4") (pinfunction "4_4") (pintype "bidirectional"))
    )
    (net (code "57") (name "unconnected-(J2-3-Pad18)") (class "Default")
      (node (ref "J2") (pin "18") (pinfunction "3_18") (pintype "bidirectional"))
    )
    (net (code "58") (name "unconnected-(J2-5-Pad16)") (class "Default")
      (node (ref "J2") (pin "16") (pinfunction "5_16") (pintype "bidirectional"))
    )
    (net (code "59") (name "unconnected-(J2-7-Pad14)") (class "Default")
      (node (ref "J2") (pin "14") (pinfunction "7_14") (pintype "bidirectional"))
    )
    (net (code "60") (name "unconnected-(J2-9-Pad12)") (class "Default")
      (node (ref "J2") (pin "12") (pinfunction "9_12") (pintype "bidirectional"))
    )
    (net (code "61") (name "unconnected-(J3-7-Pad27)") (class "Default")
      (node (ref "J3") (pin "27") (pinfunction "7_27") (pintype "bidirectional"))
    )
    (net (code "62") (name "unconnected-(J3-8-Pad28)") (class "Default")
      (node (ref "J3") (pin "28") (pinfunction "8_28") (pintype "bidirectional"))
    )
    (net (code "63") (name "unconnected-(J3-9-Pad29)") (class "Default")
      (node (ref "J3") (pin "29") (pinfunction "9_29") (pintype "bidirectional"))
    )
    (net (code "64") (name "unconnected-(J3-10-Pad30)") (class "Default")
      (node (ref "J3") (pin "30") (pinfunction "10_30") (pintype "bidirectional"))
    )
    (net (code "65") (name "unconnected-(J4-5-Pad36)") (class "Default")
      (node (ref "J4") (pin "36") (pinfunction "5_36") (pintype "bidirectional"))
    )
    (net (code "66") (name "unconnected-(J4-6-Pad35)") (class "Default")
      (node (ref "J4") (pin "35") (pinfunction "6_35") (pintype "bidirectional"))
    )
    (net (code "67") (name "unconnected-(U3-NC-Pad5)") (class "Default")
      (node (ref "U3") (pin "5") (pinfunction "NC_5") (pintype "bidirectional"))
    )
    (net (code "68") (name "unconnected-(U3-NC-Pad10)") (class "Default")
      (node (ref "U3") (pin "10") (pinfunction "NC_10") (pintype "bidirectional"))
    )
    (net (code "69") (name "~{LCD_CS}") (class "Default")
      (node (ref "J2") (pin "13") (pinfunction "8_13") (pintype "bidirectional"))
      (node (ref "J6") (pin "6") (pinfunction "~{CS}_6") (pintype "bidirectional"))
    )
    (net (code "70") (name "~{LCD_RST}") (class "Default")
      (node (ref "J2") (pin "17") (pinfunction "4_17") (pintype "bidirectional"))
      (node (ref "R34") (pin "1") (pinfunction "1_1") (pintype "passive"))
    )
    (net (code "71") (name "~{LIGHT_INT}") (class "Default")
      (node (ref "J1") (pin "8") (pinfunction "8_8") (pintype "bidirectional"))
      (node (ref "R6") (pin "1") (pinfunction "1_1") (pintype "passive"))
      (node (ref "U2") (pin "5") (pinfunction "~{INT}_5") (pintype "output"))
    )
    (net (code "72") (name "~{TEMP_DRDY}") (class "Default")
      (node (ref "J2") (pin "11") (pinfunction "10_11") (pintype "bidirectional"))
      (node (ref "R1") (pin "1") (pinfunction "1_1") (pintype "passive"))
      (node (ref "U1") (pin "C2") (pinfunction "~{DRDY}_C2") (pintype "output"))
    )
  )
)
